# teensy.net
KiCad netlist of a schematic drawn in Altium Designer
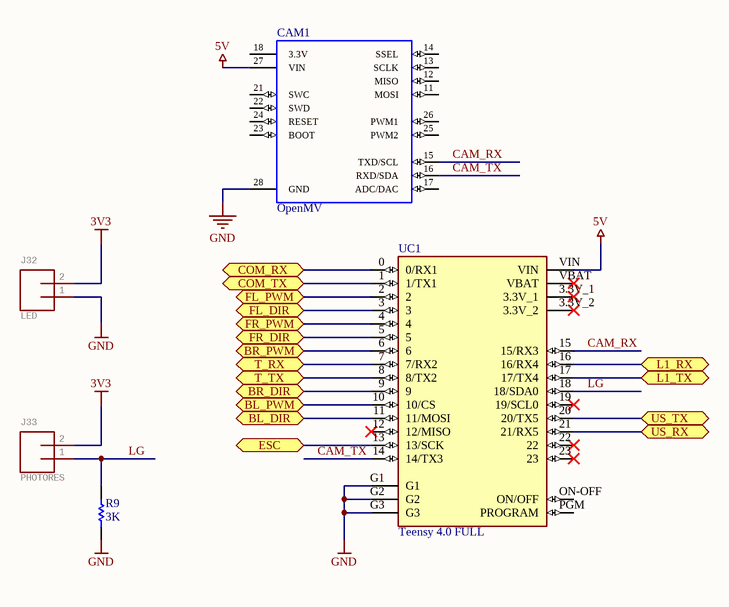
[diagram p0: teensy.SchDoc]

(export (version "E")
  (design (tool "Eeschema 10.0.6"))
  (components
    (comp (ref "CAM1")
      (value "OpenMV")
      (footprint "OPENMV3")
      (libsource (lib "Integrated_Library1") (part "OpenMV"))
    )
    (comp (ref "J32")
      (value "LED")
      (footprint "1X02_LOCK")
      (libsource (lib "Integrated_Library1") (part "CONN_02LOCK"))
    )
    (comp (ref "J33")
      (value "PHOTORES")
      (footprint "1X02_LOCK")
      (libsource (lib "Integrated_Library1") (part "CONN_02LOCK"))
    )
    (comp (ref "R9")
      (value "3K")
      (footprint "RES0603")
      (description "Resistor")
      (libsource (lib "Integrated_Library1") (part "RES0603"))
    )
    (comp (ref "UC1")
      (value "Teensy 4.0 FULL")
      (footprint "MODULE_DEV-15583")
      (description "RT1062 Teensy 4.0 i.MX ARMÂ® CortexÂ®-M7 MPU Embedded Evaluation Board")
      (fields (field (name "DIGI-KEY_PART_NUMBER") "1568-DEV-15583-ND") (field (name "MP") "DEV-15583"))
      (libsource (lib "Integrated_Library1") (part "Teensy 4.0"))
    )
  )
  (nets
    (net (code "1") (name "/BL_DIR") (class "Default")
      (node (ref "UC1") (pin "11") (pinfunction "11/MOSI_11") (pintype "bidirectional"))
    )
    (net (code "2") (name "/BL_PWM") (class "Default")
      (node (ref "UC1") (pin "10") (pinfunction "10/CS_10") (pintype "bidirectional"))
    )
    (net (code "3") (name "/BR_DIR") (class "Default")
      (node (ref "UC1") (pin "9") (pinfunction "9_9") (pintype "bidirectional"))
    )
    (net (code "4") (name "/BR_PWM") (class "Default")
      (node (ref "UC1") (pin "6") (pinfunction "6_6") (pintype "bidirectional"))
    )
    (net (code "5") (name "/CAM_RX") (class "Default")
      (node (ref "CAM1") (pin "15") (pinfunction "TXD/SCL_15") (pintype "bidirectional"))
      (node (ref "UC1") (pin "15") (pinfunction "15/RX3_15") (pintype "bidirectional"))
    )
    (net (code "6") (name "/CAM_TX") (class "Default")
      (node (ref "CAM1") (pin "16") (pinfunction "RXD/SDA_16") (pintype "bidirectional"))
      (node (ref "UC1") (pin "14") (pinfunction "14/TX3_14") (pintype "bidirectional"))
    )
    (net (code "7") (name "/COM_RX") (class "Default")
      (node (ref "UC1") (pin "0") (pinfunction "0/RX1_0") (pintype "bidirectional"))
    )
    (net (code "8") (name "/COM_TX") (class "Default")
      (node (ref "UC1") (pin "1") (pinfunction "1/TX1_1") (pintype "bidirectional"))
    )
    (net (code "9") (name "/ESC") (class "Default")
      (node (ref "UC1") (pin "13") (pinfunction "13/SCK_13") (pintype "bidirectional"))
    )
    (net (code "10") (name "/FL_DIR") (class "Default")
      (node (ref "UC1") (pin "3") (pinfunction "3_3") (pintype "bidirectional"))
    )
    (net (code "11") (name "/FL_PWM") (class "Default")
      (node (ref "UC1") (pin "2") (pinfunction "2_2") (pintype "bidirectional"))
    )
    (net (code "12") (name "/FR_DIR") (class "Default")
      (node (ref "UC1") (pin "5") (pinfunction "5_5") (pintype "bidirectional"))
    )
    (net (code "13") (name "/FR_PWM") (class "Default")
      (node (ref "UC1") (pin "4") (pinfunction "4_4") (pintype "bidirectional"))
    )
    (net (code "14") (name "/L1_RX") (class "Default")
      (node (ref "UC1") (pin "16") (pinfunction "16/RX4_16") (pintype "bidirectional"))
    )
    (net (code "15") (name "/L1_TX") (class "Default")
      (node (ref "UC1") (pin "17") (pinfunction "17/TX4_17") (pintype "bidirectional"))
    )
    (net (code "16") (name "/LG") (class "Default")
      (node (ref "J33") (pin "1") (pinfunction "1_1") (pintype "passive"))
      (node (ref "R9") (pin "2") (pinfunction "2_2") (pintype "passive"))
      (node (ref "UC1") (pin "18") (pinfunction "18/SDA0_18") (pintype "bidirectional"))
    )
    (net (code "17") (name "/T_RX") (class "Default")
      (node (ref "UC1") (pin "7") (pinfunction "7/RX2_7") (pintype "bidirectional"))
    )
    (net (code "18") (name "/T_TX") (class "Default")
      (node (ref "UC1") (pin "8") (pinfunction "8/TX2_8") (pintype "bidirectional"))
    )
    (net (code "19") (name "/US_RX") (class "Default")
      (node (ref "UC1") (pin "21") (pinfunction "21/RX5_21") (pintype "bidirectional"))
    )
    (net (code "20") (name "/US_TX") (class "Default")
      (node (ref "UC1") (pin "20") (pinfunction "20/TX5_20") (pintype "bidirectional"))
    )
    (net (code "21") (name "3V3") (class "Default")
      (node (ref "J32") (pin "2") (pinfunction "2_2") (pintype "passive"))
      (node (ref "J33") (pin "2") (pinfunction "2_2") (pintype "passive"))
    )
    (net (code "22") (name "5V") (class "Default")
      (node (ref "CAM1") (pin "27") (pinfunction "VIN_27") (pintype "power_in"))
      (node (ref "UC1") (pin "VIN") (pinfunction "VIN_VIN") (pintype "power_in"))
    )
    (net (code "23") (name "GND") (class "Default")
      (node (ref "CAM1") (pin "28") (pinfunction "GND_28") (pintype "power_in"))
      (node (ref "J32") (pin "1") (pinfunction "1_1") (pintype "passive"))
      (node (ref "R9") (pin "1") (pinfunction "1_1") (pintype "passive"))
      (node (ref "UC1") (pin "G1") (pinfunction "G1_G1") (pintype "power_in"))
      (node (ref "UC1") (pin "G2") (pinfunction "G2_G2") (pintype "power_in"))
      (node (ref "UC1") (pin "G3") (pinfunction "G3_G3") (pintype "power_in"))
    )
    (net (code "24") (name "unconnected-(CAM1-3.3V-Pad18)") (class "Default")
      (node (ref "CAM1") (pin "18") (pinfunction "3.3V_18") (pintype "power_in"))
    )
    (net (code "25") (name "unconnected-(CAM1-ADC{slash}DAC-Pad17)") (class "Default")
      (node (ref "CAM1") (pin "17") (pinfunction "ADC/DAC_17") (pintype "bidirectional"))
    )
    (net (code "26") (name "unconnected-(CAM1-BOOT-Pad23)") (class "Default")
      (node (ref "CAM1") (pin "23") (pinfunction "BOOT_23") (pintype "bidirectional"))
    )
    (net (code "27") (name "unconnected-(CAM1-MISO-Pad12)") (class "Default")
      (node (ref "CAM1") (pin "12") (pinfunction "MISO_12") (pintype "bidirectional"))
    )
    (net (code "28") (name "unconnected-(CAM1-MOSI-Pad11)") (class "Default")
      (node (ref "CAM1") (pin "11") (pinfunction "MOSI_11") (pintype "bidirectional"))
    )
    (net (code "29") (name "unconnected-(CAM1-PWM1-Pad26)") (class "Default")
      (node (ref "CAM1") (pin "26") (pinfunction "PWM1_26") (pintype "bidirectional"))
    )
    (net (code "30") (name "unconnected-(CAM1-PWM2-Pad25)") (class "Default")
      (node (ref "CAM1") (pin "25") (pinfunction "PWM2_25") (pintype "bidirectional"))
    )
    (net (code "31") (name "unconnected-(CAM1-RESET-Pad24)") (class "Default")
      (node (ref "CAM1") (pin "24") (pinfunction "RESET_24") (pintype "bidirectional"))
    )
    (net (code "32") (name "unconnected-(CAM1-SCLK-Pad13)") (class "Default")
      (node (ref "CAM1") (pin "13") (pinfunction "SCLK_13") (pintype "bidirectional"))
    )
    (net (code "33") (name "unconnected-(CAM1-SSEL-Pad14)") (class "Default")
      (node (ref "CAM1") (pin "14") (pinfunction "SSEL_14") (pintype "bidirectional"))
    )
    (net (code "34") (name "unconnected-(CAM1-SWC-Pad21)") (class "Default")
      (node (ref "CAM1") (pin "21") (pinfunction "SWC_21") (pintype "bidirectional"))
    )
    (net (code "35") (name "unconnected-(CAM1-SWD-Pad22)") (class "Default")
      (node (ref "CAM1") (pin "22") (pinfunction "SWD_22") (pintype "bidirectional"))
    )
    (net (code "36") (name "unconnected-(UC1-12{slash}MISO-Pad12)") (class "Default")
      (node (ref "UC1") (pin "12") (pinfunction "12/MISO_12") (pintype "bidirectional+no_connect"))
    )
    (net (code "37") (name "unconnected-(UC1-19{slash}SCL0-Pad19)") (class "Default")
      (node (ref "UC1") (pin "19") (pinfunction "19/SCL0_19") (pintype "bidirectional+no_connect"))
    )
    (net (code "38") (name "unconnected-(UC1-ON{slash}OFF-PadON-OFF)") (class "Default")
      (node (ref "UC1") (pin "ON-OFF") (pinfunction "ON/OFF_ON-OFF") (pintype "bidirectional"))
    )
    (net (code "39") (name "unconnected-(UC1-PROGRAM-PadPGM)") (class "Default")
      (node (ref "UC1") (pin "PGM") (pinfunction "PROGRAM_PGM") (pintype "bidirectional"))
    )
    (net (code "40") (name "unconnected-(UC1-Pad3.3V_1)") (class "Default")
      (node (ref "UC1") (pin "3.3V_1") (pinfunction "3.3V_1_3.3V_1") (pintype "power_in+no_connect"))
    )
    (net (code "41") (name "unconnected-(UC1-Pad3.3V_2)") (class "Default")
      (node (ref "UC1") (pin "3.3V_2") (pinfunction "3.3V_2_3.3V_2") (pintype "power_in+no_connect"))
    )
    (net (code "42") (name "unconnected-(UC1-Pad22)") (class "Default")
      (node (ref "UC1") (pin "22") (pinfunction "22_22") (pintype "bidirectional+no_connect"))
    )
    (net (code "43") (name "unconnected-(UC1-Pad23)") (class "Default")
      (node (ref "UC1") (pin "23") (pinfunction "23_23") (pintype "bidirectional+no_connect"))
    )
    (net (code "44") (name "unconnected-(UC1-PadVBAT)") (class "Default")
      (node (ref "UC1") (pin "VBAT") (pinfunction "VBAT_VBAT") (pintype "power_in+no_connect"))
    )
  )
)
